# single_pwm_mosfet_driver_with_npn_booste.net
KiCad netlist of a schematic drawn in EAGLE
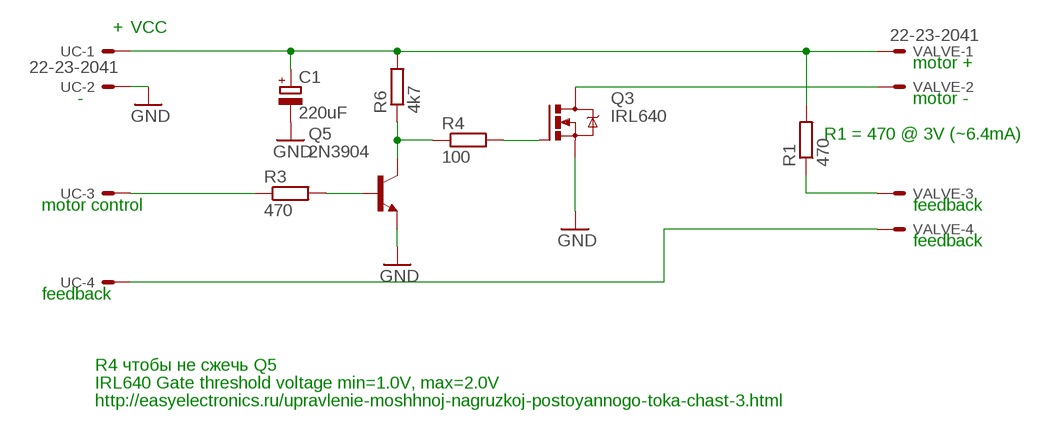
[diagram p0: schematic, sheet 1]

(export (version "E")
  (design (tool "Eeschema 10.0.6"))
  (components
    (comp (ref "C1")
      (value "220uF")
      (footprint "eagle-import:E2,5-7")
      (libsource (lib "eagle-import") (part "CPOL-EUE2.5-7"))
    )
    (comp (ref "Q3")
      (value "IRL640")
      (footprint "eagle-import:TO220BV")
      (libsource (lib "eagle-import") (part "IRF740"))
    )
    (comp (ref "Q5")
      (value "2N3904")
      (footprint "eagle-import:TO92")
      (libsource (lib "eagle-import") (part "2N3904"))
    )
    (comp (ref "R1")
      (value "470")
      (footprint "eagle-import:0207_7")
      (libsource (lib "eagle-import") (part "R-EU_0207/7"))
    )
    (comp (ref "R3")
      (value "470")
      (footprint "eagle-import:0207_7")
      (libsource (lib "eagle-import") (part "R-EU_0207/7"))
    )
    (comp (ref "R4")
      (value "100")
      (footprint "eagle-import:0207_7")
      (libsource (lib "eagle-import") (part "R-EU_0207/7"))
    )
    (comp (ref "R6")
      (value "4k7")
      (footprint "eagle-import:0207_7")
      (libsource (lib "eagle-import") (part "R-EU_0207/7"))
    )
    (comp (ref "UC")
      (value "22-23-2041")
      (footprint "eagle-import:22-23-2041")
      (fields (field (name "MF") "MOLEX"))
      (libsource (lib "eagle-import") (part "22-23-2041"))
    )
    (comp (ref "VALVE")
      (value "22-23-2041")
      (footprint "eagle-import:22-23-2041")
      (fields (field (name "MF") "MOLEX"))
      (libsource (lib "eagle-import") (part "22-23-2041"))
    )
  )
  (nets
    (net (code "1") (name "GND") (class "Default")
      (node (ref "C1") (pin "-") (pinfunction "-_-") (pintype "passive"))
      (node (ref "Q3") (pin "S") (pinfunction "S_S") (pintype "passive"))
      (node (ref "Q5") (pin "3") (pinfunction "E_3") (pintype "passive"))
      (node (ref "UC") (pin "2") (pinfunction "S_2") (pintype "passive"))
    )
    (net (code "2") (name "Net-(Q3-PadG)") (class "Default")
      (node (ref "Q3") (pin "G") (pinfunction "G_G") (pintype "passive"))
      (node (ref "R4") (pin "2") (pinfunction "2_2") (pintype "passive"))
    )
    (net (code "3") (name "Net-(Q5-B)") (class "Default")
      (node (ref "Q5") (pin "2") (pinfunction "B_2") (pintype "passive"))
      (node (ref "R3") (pin "2") (pinfunction "2_2") (pintype "passive"))
    )
    (net (code "4") (name "Net-(Q5-C)") (class "Default")
      (node (ref "Q5") (pin "1") (pinfunction "C_1") (pintype "passive"))
      (node (ref "R4") (pin "1") (pinfunction "1_1") (pintype "passive"))
      (node (ref "R6") (pin "1") (pinfunction "1_1") (pintype "passive"))
    )
    (net (code "5") (name "Net-(UCA-S)") (class "Default")
      (node (ref "C1") (pin "+") (pinfunction "+_+") (pintype "passive"))
      (node (ref "R1") (pin "2") (pinfunction "2_2") (pintype "passive"))
      (node (ref "R6") (pin "2") (pinfunction "2_2") (pintype "passive"))
      (node (ref "UC") (pin "1") (pinfunction "S_1") (pintype "passive"))
      (node (ref "VALVE") (pin "1") (pinfunction "S_1") (pintype "passive"))
    )
    (net (code "6") (name "Net-(UCC-S)") (class "Default")
      (node (ref "R3") (pin "1") (pinfunction "1_1") (pintype "passive"))
      (node (ref "UC") (pin "3") (pinfunction "S_3") (pintype "passive"))
    )
    (net (code "7") (name "Net-(UCD-S)") (class "Default")
      (node (ref "UC") (pin "4") (pinfunction "S_4") (pintype "passive"))
      (node (ref "VALVE") (pin "4") (pinfunction "S_4") (pintype "passive"))
    )
    (net (code "8") (name "Net-(VALVEB-S)") (class "Default")
      (node (ref "Q3") (pin "D") (pinfunction "D_D") (pintype "passive"))
      (node (ref "VALVE") (pin "2") (pinfunction "S_2") (pintype "passive"))
    )
    (net (code "9") (name "Net-(VALVEC-S)") (class "Default")
      (node (ref "R1") (pin "1") (pinfunction "1_1") (pintype "passive"))
      (node (ref "VALVE") (pin "3") (pinfunction "S_3") (pintype "passive"))
    )
  )
)
